# Intar_IR_LED_Module.net
KiCad netlist of a schematic drawn in EAGLE
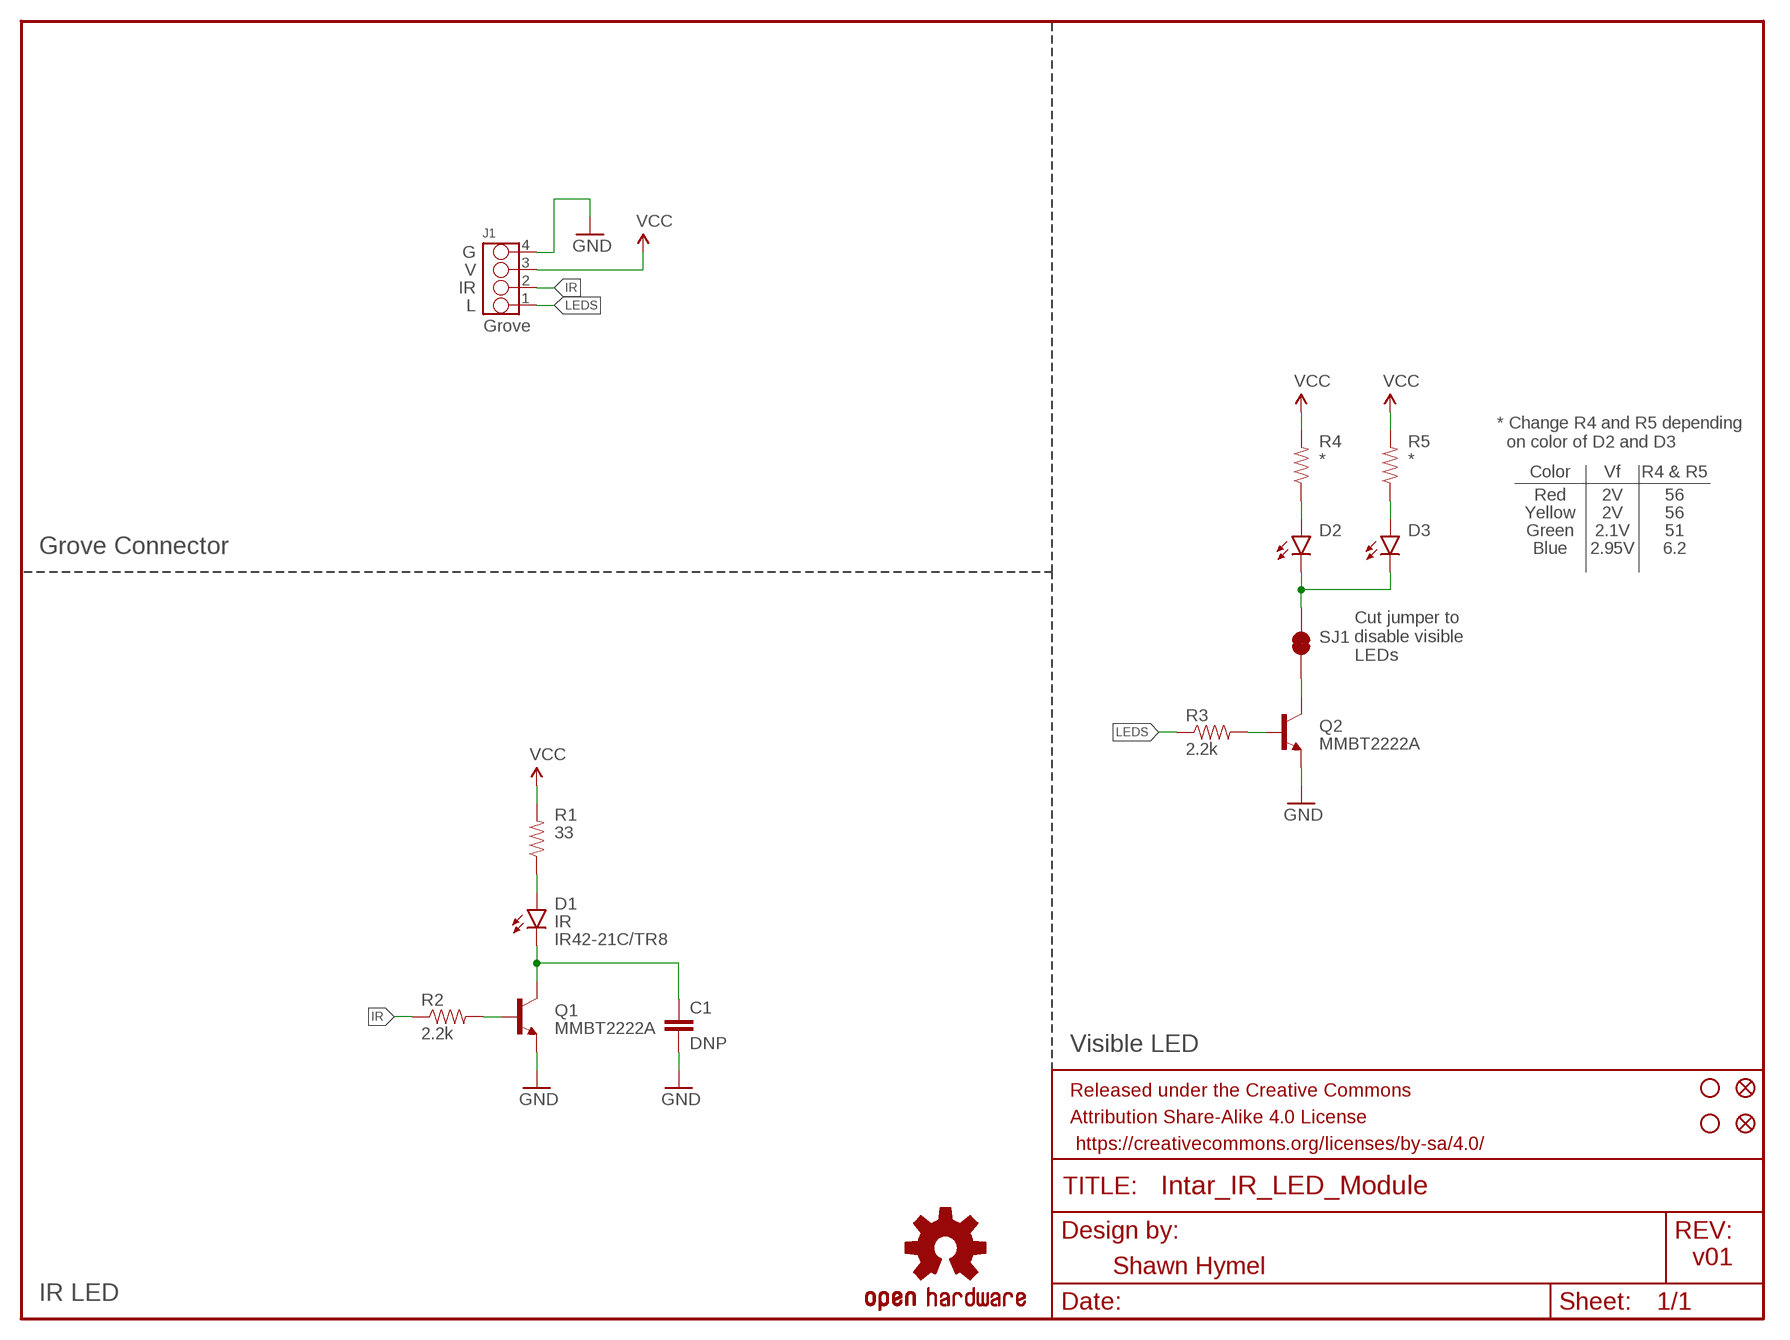
[diagram p0: schematic, sheet 1]

(export (version "E")
  (design (tool "Eeschema 10.0.6"))
  (components
    (comp (ref "C1")
      (value "DNP")
      (footprint "eagle-import:0603-CAP")
      (libsource (lib "eagle-import") (part "10NF/10000PF-50V-10%(0603)"))
    )
    (comp (ref "D1")
      (value "IR")
      (footprint "eagle-import:IR42-21C_TR8")
      (fields (field (name "MFG_NAME") "IR42-21C/TR8"))
      (libsource (lib "eagle-import") (part "LEDIR42-21C/TR8"))
    )
    (comp (ref "D2")
      (value "LED0603")
      (footprint "eagle-import:LED-0603")
      (libsource (lib "eagle-import") (part "LED0603"))
    )
    (comp (ref "D3")
      (value "LED0603")
      (footprint "eagle-import:LED-0603")
      (libsource (lib "eagle-import") (part "LED0603"))
    )
    (comp (ref "FID1")
      (value "FIDUCIAL1X2")
      (footprint "eagle-import:FIDUCIAL-1X2")
      (libsource (lib "eagle-import") (part "FIDUCIAL1X2"))
    )
    (comp (ref "FID2")
      (value "FIDUCIAL1X2")
      (footprint "eagle-import:FIDUCIAL-1X2")
      (libsource (lib "eagle-import") (part "FIDUCIAL1X2"))
    )
    (comp (ref "FRAME1")
      (value "FRAME-LETTER")
      (footprint "eagle-import:CREATIVE_COMMONS")
      (libsource (lib "eagle-import") (part "FRAME-LETTER"))
    )
    (comp (ref "J1")
      (value "GROVE-4P-2.0-3470130P1")
      (footprint "eagle-import:4P-2.0")
      (libsource (lib "eagle-import") (part "GROVE-4P-2.0-3470130P1"))
    )
    (comp (ref "LOGO1")
      (value "OSHW-LOGOS")
      (footprint "eagle-import:OSHW-LOGO-S")
      (libsource (lib "eagle-import") (part "OSHW-LOGOS"))
    )
    (comp (ref "Q1")
      (value "MMBT2222A")
      (footprint "eagle-import:SOT23-3")
      (libsource (lib "eagle-import") (part "TRANSISTOR_NPNMMBT2222A"))
    )
    (comp (ref "Q2")
      (value "MMBT2222A")
      (footprint "eagle-import:SOT23-3")
      (libsource (lib "eagle-import") (part "TRANSISTOR_NPNMMBT2222A"))
    )
    (comp (ref "R1")
      (value "33")
      (footprint "eagle-import:0603-RES")
      (libsource (lib "eagle-import") (part "RESISTOR0603-RES"))
    )
    (comp (ref "R2")
      (value "2.2k")
      (footprint "eagle-import:0603-RES")
      (libsource (lib "eagle-import") (part "2.2KOHM-1/10W-1%(0603)"))
    )
    (comp (ref "R3")
      (value "2.2k")
      (footprint "eagle-import:0603-RES")
      (libsource (lib "eagle-import") (part "2.2KOHM-1/10W-1%(0603)"))
    )
    (comp (ref "R4")
      (value "*")
      (footprint "eagle-import:0603-RES")
      (libsource (lib "eagle-import") (part "RESISTOR0603-RES"))
    )
    (comp (ref "R5")
      (value "*")
      (footprint "eagle-import:0603-RES")
      (libsource (lib "eagle-import") (part "RESISTOR0603-RES"))
    )
    (comp (ref "SJ1")
      (value "JUMPER-PAD-2-NC_BY_TRACE")
      (footprint "eagle-import:PAD-JUMPER-2-NC_BY_TRACE_YES_SILK")
      (libsource (lib "eagle-import") (part "JUMPER-PAD-2-NC_BY_TRACE"))
    )
    (comp (ref "STANDOFF1")
      (value "STAND-OFF")
      (footprint "eagle-import:STAND-OFF")
      (libsource (lib "eagle-import") (part "STAND-OFF"))
    )
    (comp (ref "STANDOFF2")
      (value "STAND-OFF")
      (footprint "eagle-import:STAND-OFF")
      (libsource (lib "eagle-import") (part "STAND-OFF"))
    )
  )
  (nets
    (net (code "1") (name "GND") (class "Default")
      (node (ref "C1") (pin "2") (pinfunction "2_2") (pintype "passive"))
      (node (ref "J1") (pin "4") (pinfunction "4_4") (pintype "bidirectional"))
      (node (ref "Q1") (pin "2") (pinfunction "E_2") (pintype "passive"))
      (node (ref "Q2") (pin "2") (pinfunction "E_2") (pintype "passive"))
    )
    (net (code "2") (name "IR") (class "Default")
      (node (ref "J1") (pin "2") (pinfunction "2_2") (pintype "bidirectional"))
      (node (ref "R2") (pin "1") (pinfunction "1_1") (pintype "passive"))
    )
    (net (code "3") (name "LEDS") (class "Default")
      (node (ref "J1") (pin "1") (pinfunction "1_1") (pintype "bidirectional"))
      (node (ref "R3") (pin "1") (pinfunction "1_1") (pintype "passive"))
    )
    (net (code "4") (name "Net-(D1-PadA)") (class "Default")
      (node (ref "D1") (pin "A") (pinfunction "A_A") (pintype "passive"))
      (node (ref "R1") (pin "1") (pinfunction "1_1") (pintype "passive"))
    )
    (net (code "5") (name "Net-(D2-PadA)") (class "Default")
      (node (ref "D2") (pin "A") (pinfunction "A_A") (pintype "passive"))
      (node (ref "R4") (pin "1") (pinfunction "1_1") (pintype "passive"))
    )
    (net (code "6") (name "Net-(D2-PadC)") (class "Default")
      (node (ref "D2") (pin "C") (pinfunction "C_C") (pintype "passive"))
      (node (ref "D3") (pin "C") (pinfunction "C_C") (pintype "passive"))
      (node (ref "SJ1") (pin "2") (pinfunction "2_2") (pintype "passive"))
    )
    (net (code "7") (name "Net-(D3-PadA)") (class "Default")
      (node (ref "D3") (pin "A") (pinfunction "A_A") (pintype "passive"))
      (node (ref "R5") (pin "1") (pinfunction "1_1") (pintype "passive"))
    )
    (net (code "8") (name "Net-(Q1-B)") (class "Default")
      (node (ref "Q1") (pin "1") (pinfunction "B_1") (pintype "passive"))
      (node (ref "R2") (pin "2") (pinfunction "2_2") (pintype "passive"))
    )
    (net (code "9") (name "Net-(Q1-C)") (class "Default")
      (node (ref "C1") (pin "1") (pinfunction "1_1") (pintype "passive"))
      (node (ref "D1") (pin "C") (pinfunction "C_C") (pintype "passive"))
      (node (ref "Q1") (pin "3") (pinfunction "C_3") (pintype "passive"))
    )
    (net (code "10") (name "Net-(Q2-B)") (class "Default")
      (node (ref "Q2") (pin "1") (pinfunction "B_1") (pintype "passive"))
      (node (ref "R3") (pin "2") (pinfunction "2_2") (pintype "passive"))
    )
    (net (code "11") (name "Net-(Q2-C)") (class "Default")
      (node (ref "Q2") (pin "3") (pinfunction "C_3") (pintype "passive"))
      (node (ref "SJ1") (pin "1") (pinfunction "1_1") (pintype "passive"))
    )
    (net (code "12") (name "VCC") (class "Default")
      (node (ref "J1") (pin "3") (pinfunction "3_3") (pintype "bidirectional"))
      (node (ref "R1") (pin "2") (pinfunction "2_2") (pintype "passive"))
      (node (ref "R4") (pin "2") (pinfunction "2_2") (pintype "passive"))
      (node (ref "R5") (pin "2") (pinfunction "2_2") (pintype "passive"))
    )
  )
)
